# SH6_-_3_3V_BUCK_CONVERTER.net
KiCad netlist of a schematic drawn in Altium Designer
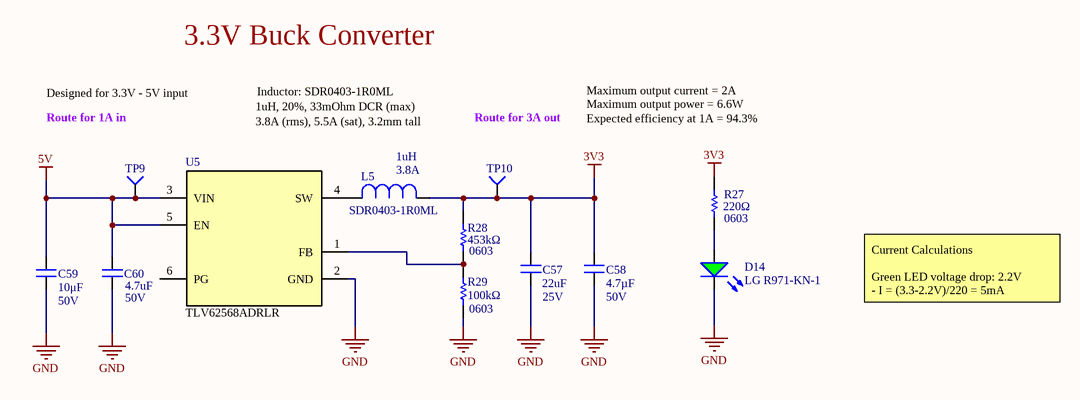
[diagram p0: SH6 - 3.3V BUCK CONVERTER.SchDoc]

(export (version "E")
  (design (tool "Eeschema 10.0.6"))
  (components
    (comp (ref "C57")
      (value "GRM32ER71E226ME15K")
      (footprint "CAPC3225X270N")
      (description "CAP CER 22UF 25V X7R 1210")
      (fields
        (field (name "TOLERANCE") "±20%")
        (field (name "VOLTAGE") "25V")
        (field (name "CAPACITANCE") "22uF")
      )
      (libsource (lib "UWRT_Schematic_Library_2020") (part "GRM32ER71E226ME15K"))
    )
    (comp (ref "C58")
      (value "4.7µF")
      (footprint "CAP1206")
      (description "CAP CER 4.7UF 50V X7R 1206")
      (fields (field (name "TOLERANCE") "10%") (field (name "VOLTAGE") "50V"))
      (libsource (lib "UWRT_Schematic_Library_2020") (part "CAP_4.7µF_50V_1206"))
    )
    (comp (ref "C59")
      (value "10μF")
      (footprint "CAP1206")
      (description "CAP CER 10UF 50V X5R 1206")
      (fields (field (name "VOLTAGE RATING") "50V") (field (name "Comment") "10uF"))
      (libsource (lib "UWRT_Schematic_Library_2020") (part "CAP_10uF_50V_1206"))
    )
    (comp (ref "C60")
      (value "4.7µF")
      (footprint "CAP1206")
      (description "CAP CER 4.7UF 50V X7R 1206")
      (fields
        (field (name "CAPACITANCE") "4.7uF")
        (field (name "TOLERANCE") "10%")
        (field (name "VOLTAGE") "50V")
      )
      (libsource (lib "UWRT_Schematic_Library_2020") (part "CAP_4.7µF_50V_1206"))
    )
    (comp (ref "D14")
      (value "LG R971-KN-1")
      (footprint "LED_0805_GREEN")
      (description "LED GREEN DIFFUSED 0805 SMD")
      (libsource (lib "UWRT_Schematic_Library_2020") (part "DIO_LED_G"))
    )
    (comp (ref "L5")
      (value "1uH")
      (footprint "IND_BOURNS_SDR04")
      (description "FIXED IND 1UH 3.8A 33 MOHM SMD")
      (fields
        (field (name "MANUFACTURER PART NUMBER 1") "SDR0403-1R0ML")
        (field (name "TOLERANCE") "±20%")
        (field (name "CURRENT RATING") "3.8A")
        (field (name "Comment") "IND_1uH_3.8A")
      )
      (libsource (lib "UWRT_Schematic_Library_2020") (part "IND_1uH_3.8A"))
    )
    (comp (ref "R27")
      (value "220Ω")
      (footprint "RESC0603(1608)_N")
      (description "RES SMD 220 OHM 5% 1/10W 0603")
      (fields
        (field (name "TOLERANCE") "5%")
        (field (name "CASE CODE (IMPERIAL)") "0603")
        (field (name "Comment") "RES_220Ω_0603")
      )
      (libsource (lib "UWRT_Schematic_Library_2020") (part "RES_220Ω_0603"))
    )
    (comp (ref "R28")
      (value "453kΩ")
      (footprint "RESC0603(1608)_N")
      (description "RES SMD 453K OHM 1% 1/10W 0603")
      (fields
        (field (name "PACKAGE") "0603")
        (field (name "TOLERANCE") "1%")
        (field (name "Comment") "RES_453kΩ_0603")
      )
      (libsource (lib "UWRT_Schematic_Library_2020") (part "RES_453kΩ_0603"))
    )
    (comp (ref "R29")
      (value "100kΩ")
      (footprint "RESC0603(1608)_N")
      (description "RES SMD 100K OHM 1% 1/10W 0603")
      (fields
        (field (name "PACKAGE") "0603")
        (field (name "TOLERANCE") "1%")
        (field (name "Comment") "RES_100kΩ_0603_1%")
      )
      (libsource (lib "UWRT_Schematic_Library_2020") (part "RES_100kΩ_0603_1%"))
    )
    (comp (ref "TP9")
      (value "TESTPOINT_SMD_LOOP")
      (footprint "S1751-46R")
      (description "PC TEST POINT SMD")
      (libsource (lib "UWRT_Schematic_Library_2020") (part "TESTPOINT_SMD_LOOP"))
    )
    (comp (ref "TP10")
      (value "TESTPOINT_SMD_LOOP")
      (footprint "S1751-46R")
      (description "PC TEST POINT SMD")
      (libsource (lib "UWRT_Schematic_Library_2020") (part "TESTPOINT_SMD_LOOP"))
    )
    (comp (ref "U5")
      (value "TLV62568ADRLR")
      (footprint "SOT50P160X60-6N")
      (description "IC REG BUCK ADJUSTABLE 2A SOT563")
      (fields (field (name "MANUFACTURER PART NUMBER 1") "TLV62568ADRLR"))
      (libsource (lib "UWRT_Schematic_Library_2020") (part "TLV62568ADRLR"))
    )
  )
  (nets
    (net (code "1") (name "3V3") (class "Default")
      (node (ref "C57") (pin "2") (pinfunction "2_2") (pintype "passive"))
      (node (ref "C58") (pin "2") (pinfunction "2_2") (pintype "passive"))
      (node (ref "L5") (pin "2") (pinfunction "2_2") (pintype "passive"))
      (node (ref "R27") (pin "2") (pinfunction "2_2") (pintype "passive"))
      (node (ref "R28") (pin "2") (pinfunction "2_2") (pintype "passive"))
      (node (ref "TP10") (pin "1") (pinfunction "=value_1") (pintype "passive"))
    )
    (net (code "2") (name "5V") (class "Default")
      (node (ref "C59") (pin "2") (pinfunction "2_2") (pintype "passive"))
      (node (ref "C60") (pin "2") (pinfunction "2_2") (pintype "passive"))
      (node (ref "TP9") (pin "1") (pinfunction "=value_1") (pintype "passive"))
      (node (ref "U5") (pin "3") (pinfunction "VIN_3") (pintype "power_in"))
      (node (ref "U5") (pin "5") (pinfunction "EN_5") (pintype "passive"))
    )
    (net (code "3") (name "GND") (class "Default")
      (node (ref "C57") (pin "1") (pinfunction "1_1") (pintype "passive"))
      (node (ref "C58") (pin "1") (pinfunction "1_1") (pintype "passive"))
      (node (ref "C59") (pin "1") (pinfunction "1_1") (pintype "passive"))
      (node (ref "C60") (pin "1") (pinfunction "1_1") (pintype "passive"))
      (node (ref "D14") (pin "2") (pinfunction "K_2") (pintype "passive"))
      (node (ref "R29") (pin "1") (pinfunction "1_1") (pintype "passive"))
      (node (ref "U5") (pin "2") (pinfunction "GND_2") (pintype "power_in"))
    )
    (net (code "4") (name "Net-(D14-A)") (class "Default")
      (node (ref "D14") (pin "1") (pinfunction "A_1") (pintype "passive"))
      (node (ref "R27") (pin "1") (pinfunction "1_1") (pintype "passive"))
    )
    (net (code "5") (name "Net-(U5-FB)") (class "Default")
      (node (ref "R28") (pin "1") (pinfunction "1_1") (pintype "passive"))
      (node (ref "R29") (pin "2") (pinfunction "2_2") (pintype "passive"))
      (node (ref "U5") (pin "1") (pinfunction "FB_1") (pintype "passive"))
    )
    (net (code "6") (name "Net-(U5-SW)") (class "Default")
      (node (ref "L5") (pin "1") (pinfunction "1_1") (pintype "passive"))
      (node (ref "U5") (pin "4") (pinfunction "SW_4") (pintype "power_in"))
    )
    (net (code "7") (name "unconnected-(U5-PG-Pad6)") (class "Default")
      (node (ref "U5") (pin "6") (pinfunction "PG_6") (pintype "open_collector"))
    )
  )
)
